# Water_Use_Monitor.net
KiCad netlist of a schematic drawn in EAGLE
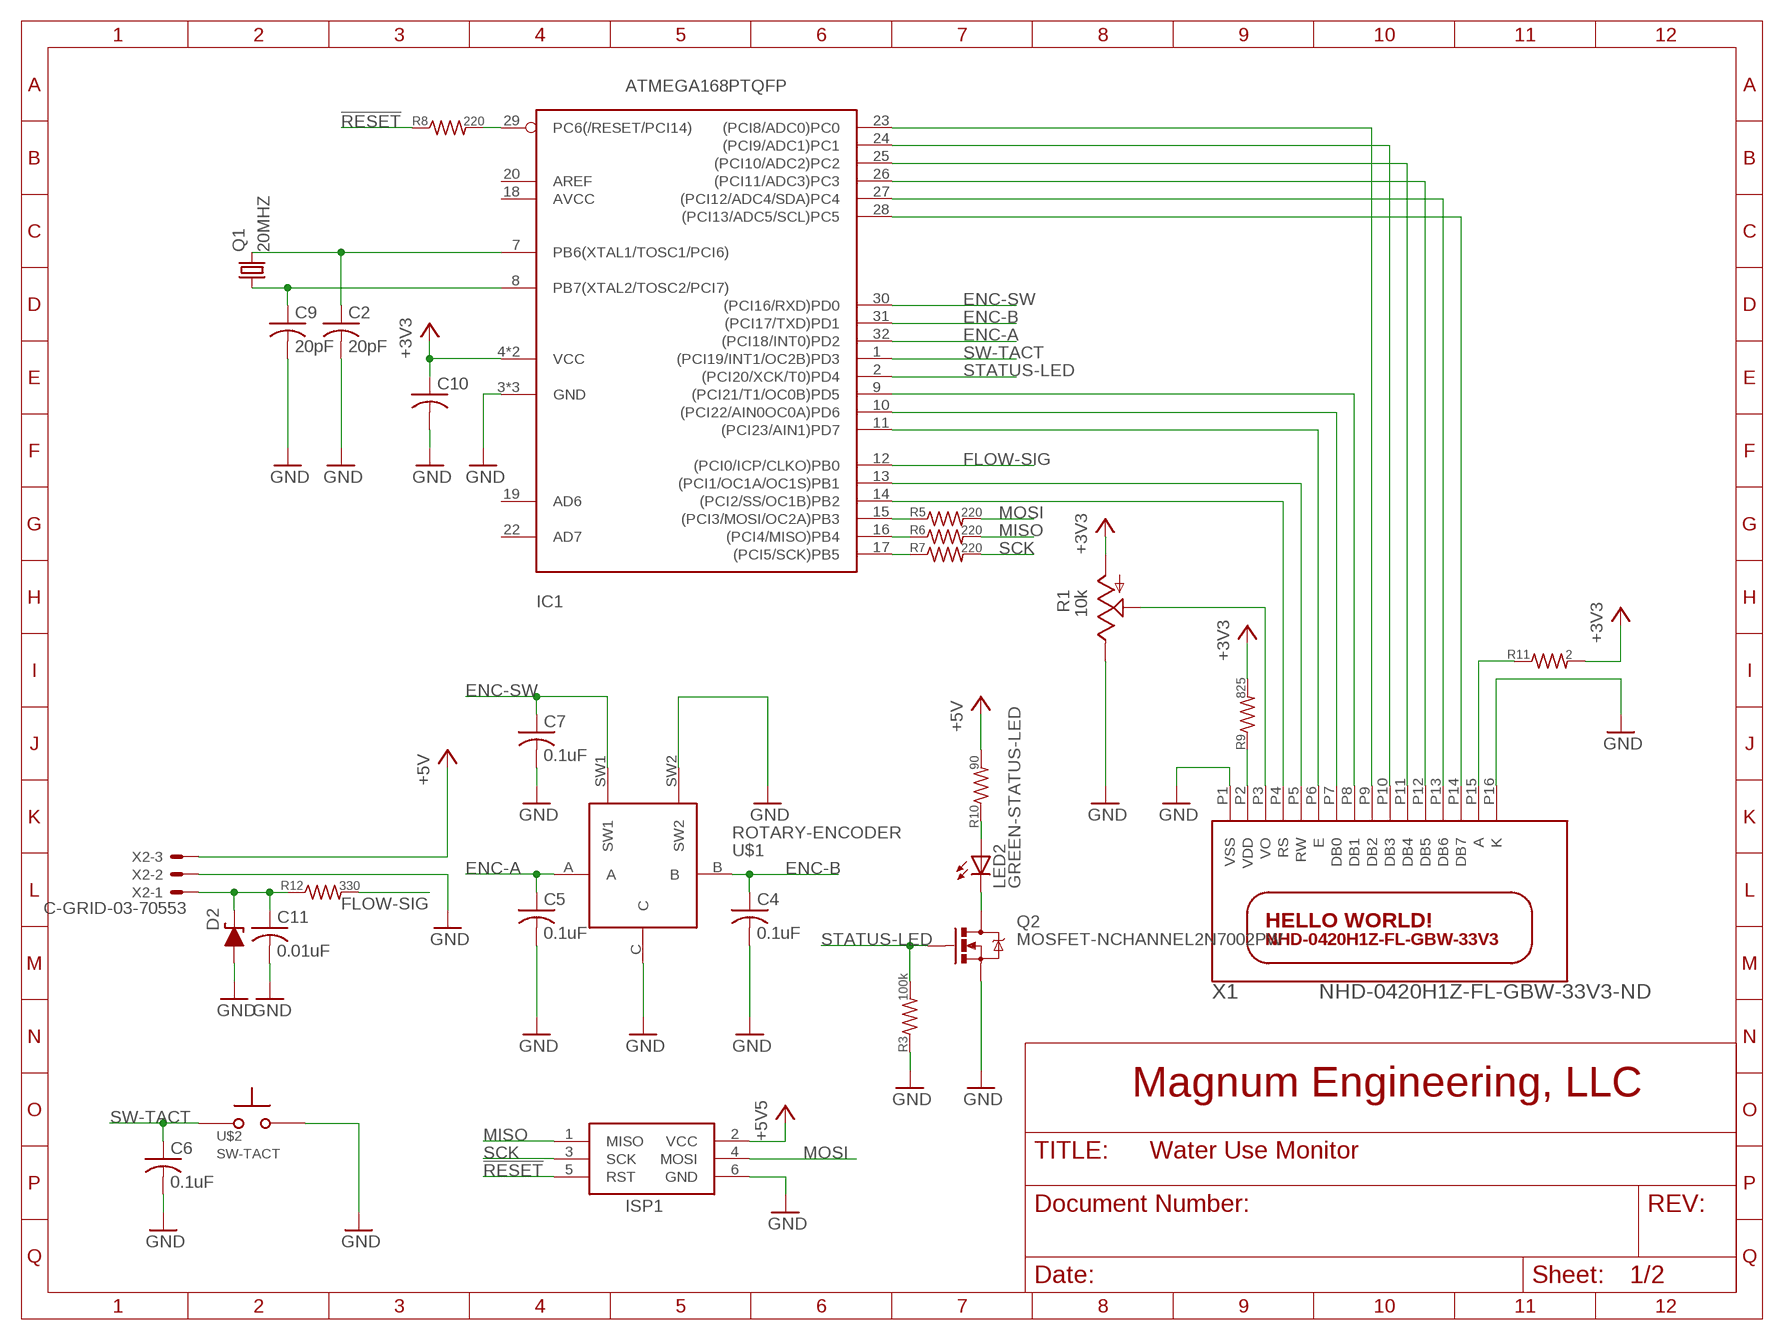
[diagram p0: schematic, sheet 1]
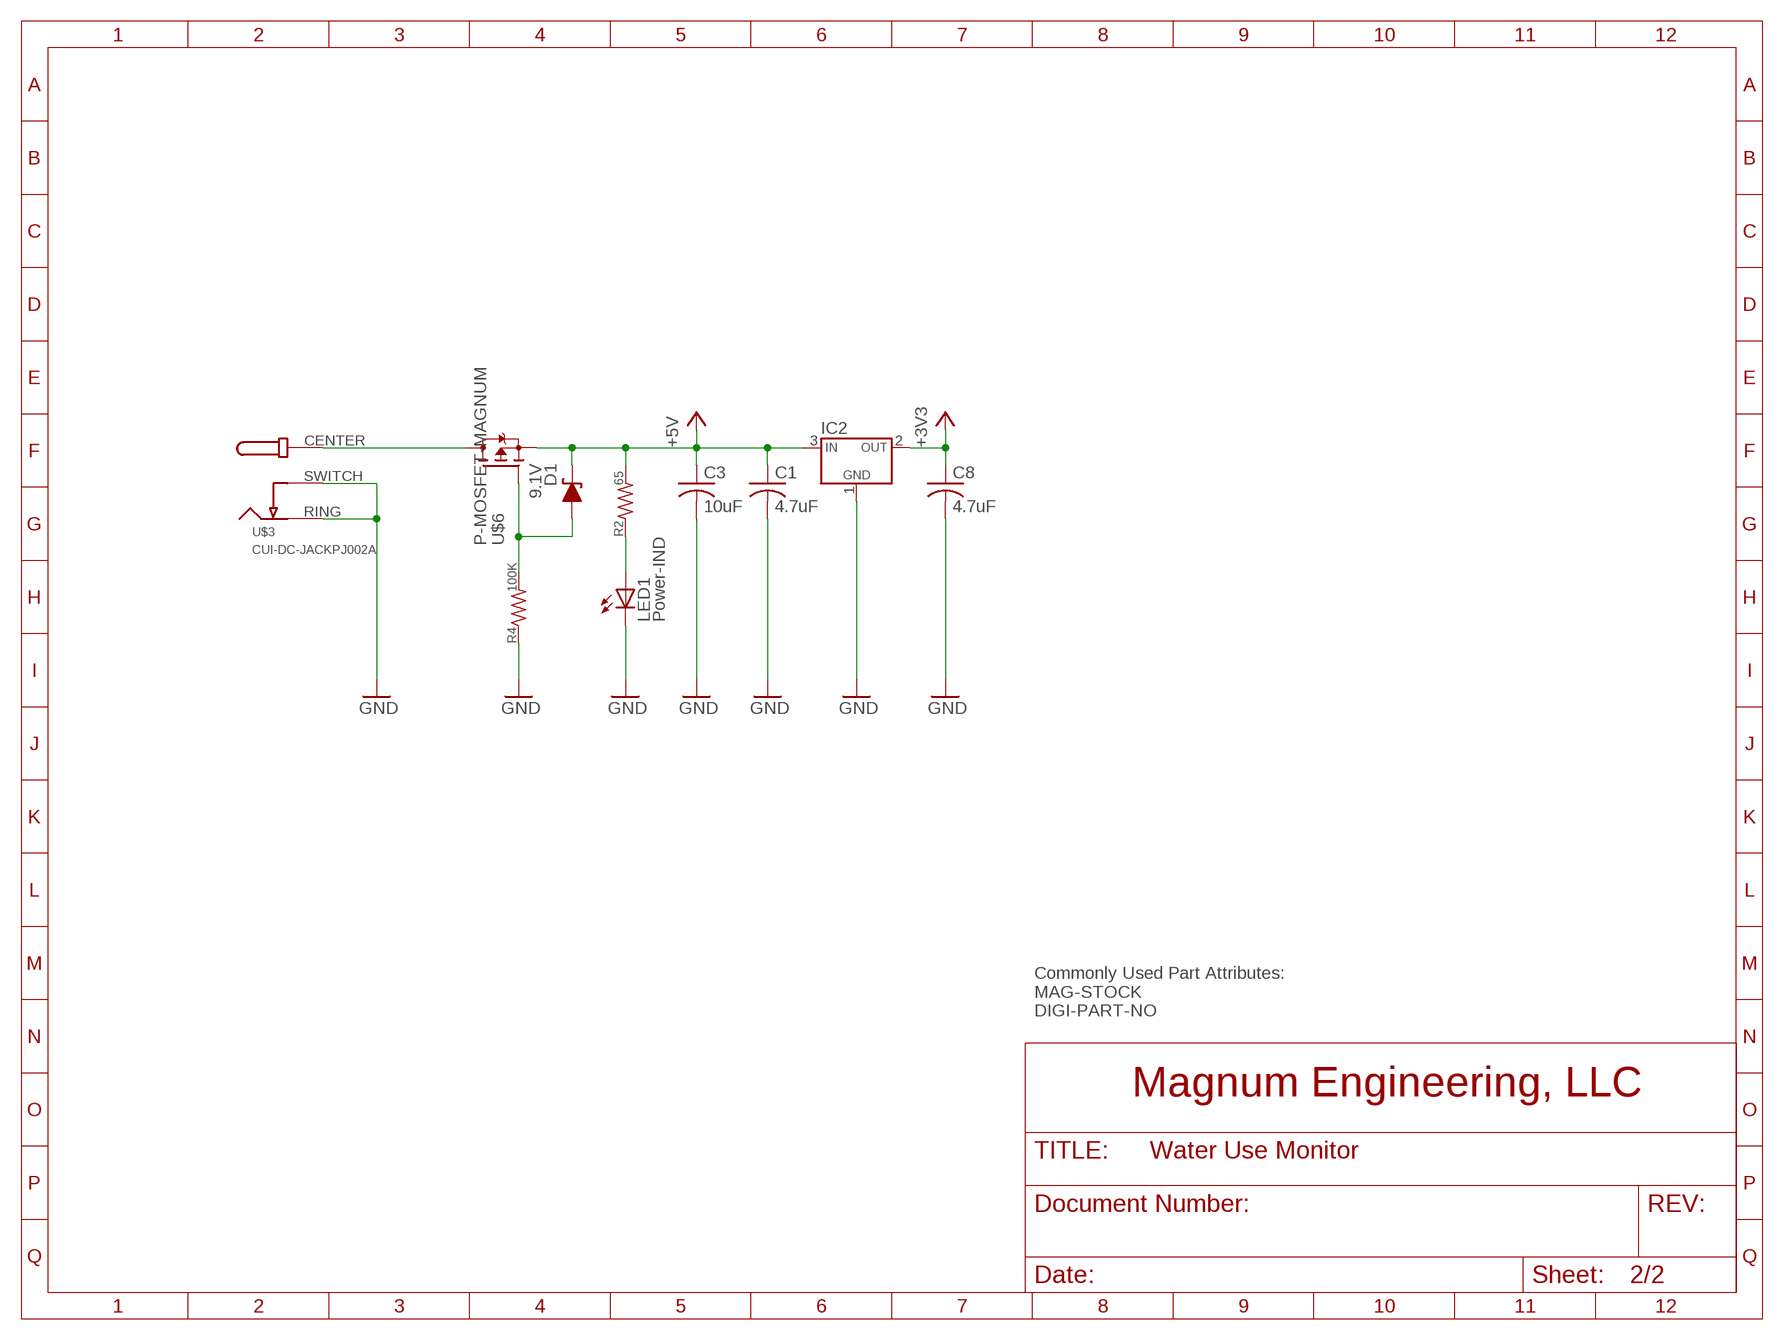
[diagram p1: schematic, sheet 2]

(export (version "E")
  (design (tool "Eeschema 10.0.6"))
  (components
    (comp (ref "C2")
      (value "20pF")
      (footprint "eagle-import:C0805")
      (libsource (lib "eagle-import") (part "CAPACITOR0805"))
    )
    (comp (ref "C4")
      (value "0.1uF")
      (footprint "eagle-import:C0805")
      (libsource (lib "eagle-import") (part "CAPACITOR0805"))
    )
    (comp (ref "C5")
      (value "0.1uF")
      (footprint "eagle-import:C0805")
      (libsource (lib "eagle-import") (part "CAPACITOR0805"))
    )
    (comp (ref "C6")
      (value "0.1uF")
      (footprint "eagle-import:C0805")
      (libsource (lib "eagle-import") (part "CAPACITOR0805"))
    )
    (comp (ref "C7")
      (value "0.1uF")
      (footprint "eagle-import:C0805")
      (libsource (lib "eagle-import") (part "CAPACITOR0805"))
    )
    (comp (ref "C9")
      (value "20pF")
      (footprint "eagle-import:C0805")
      (libsource (lib "eagle-import") (part "CAPACITOR0805"))
    )
    (comp (ref "C10")
      (value "CAPACITOR0805")
      (footprint "eagle-import:C0805")
      (libsource (lib "eagle-import") (part "CAPACITOR0805"))
    )
    (comp (ref "C11")
      (value "0.01uF")
      (footprint "eagle-import:C0805")
      (libsource (lib "eagle-import") (part "CAPACITOR0805"))
    )
    (comp (ref "D2")
      (value "ZENERSOD-123")
      (footprint "eagle-import:SOD-123")
      (libsource (lib "eagle-import") (part "ZENERSOD-123"))
    )
    (comp (ref "IC1")
      (value "ATMEGA168PTQFP")
      (footprint "eagle-import:ADS4_TQFP32-08")
      (libsource (lib "eagle-import") (part "ATMEGA168PTQFP"))
    )
    (comp (ref "ISP1")
      (value "AVRISP-6")
      (footprint "eagle-import:AVRISP")
      (libsource (lib "eagle-import") (part "AVRISP-6"))
    )
    (comp (ref "LED2")
      (value "GREEN-STATUS-LED")
      (footprint "eagle-import:LED5MM")
      (libsource (lib "eagle-import") (part "LED5MM"))
    )
    (comp (ref "Q1")
      (value "20MHZ")
      (footprint "eagle-import:20MHZ")
      (libsource (lib "eagle-import") (part "CRYSTAL"))
    )
    (comp (ref "Q2")
      (value "MOSFET-NCHANNEL2N7002PW")
      (footprint "eagle-import:SOT323")
      (libsource (lib "eagle-import") (part "MOSFET-NCHANNEL2N7002PW"))
    )
    (comp (ref "R1")
      (value "10k")
      (footprint "eagle-import:POT_RS3")
      (libsource (lib "eagle-import") (part "POTENTIOMETER"))
    )
    (comp (ref "R3")
      (value "100k")
      (footprint "eagle-import:R0805")
      (libsource (lib "eagle-import") (part "RESISTOR0805"))
    )
    (comp (ref "R5")
      (value "220")
      (footprint "eagle-import:R0805")
      (libsource (lib "eagle-import") (part "RESISTOR0805"))
    )
    (comp (ref "R6")
      (value "220")
      (footprint "eagle-import:R0805")
      (libsource (lib "eagle-import") (part "RESISTOR0805"))
    )
    (comp (ref "R7")
      (value "220")
      (footprint "eagle-import:R0805")
      (libsource (lib "eagle-import") (part "RESISTOR0805"))
    )
    (comp (ref "R8")
      (value "220")
      (footprint "eagle-import:R0805")
      (libsource (lib "eagle-import") (part "RESISTOR0805"))
    )
    (comp (ref "R9")
      (value "825")
      (footprint "eagle-import:R0805")
      (libsource (lib "eagle-import") (part "RESISTOR0805"))
    )
    (comp (ref "R10")
      (value "90")
      (footprint "eagle-import:R0805")
      (libsource (lib "eagle-import") (part "RESISTOR0805"))
    )
    (comp (ref "R11")
      (value "2")
      (footprint "eagle-import:R0805")
      (libsource (lib "eagle-import") (part "RESISTOR0805"))
    )
    (comp (ref "R12")
      (value "330")
      (footprint "eagle-import:R0805")
      (libsource (lib "eagle-import") (part "RESISTOR0805"))
    )
    (comp (ref "U$1")
      (value "ROTARY-ENCODER")
      (footprint "eagle-import:ROTARY-ENCODER")
      (libsource (lib "eagle-import") (part "ROTARY-ENCODER"))
    )
    (comp (ref "U$2")
      (value "SW-TACT")
      (footprint "eagle-import:FSM15JLH")
      (libsource (lib "eagle-import") (part "SW-TACT"))
    )
    (comp (ref "X1")
      (value "NHD-0420H1Z-FL-GBW-33V3-ND")
      (footprint "eagle-import:NEWHAVEN-LCD")
      (libsource (lib "eagle-import") (part "HD44780LCD"))
    )
    (comp (ref "X2")
      (value "C-GRID-03-70553")
      (footprint "eagle-import:70553-03")
      (libsource (lib "eagle-import") (part "C-GRID-03-70553"))
    )
    (comp (ref "C1")
      (value "4.7uF")
      (footprint "eagle-import:C0805")
      (libsource (lib "eagle-import") (part "CAPACITOR0805"))
    )
    (comp (ref "C3")
      (value "10uF")
      (footprint "eagle-import:C0805")
      (libsource (lib "eagle-import") (part "CAPACITOR0805"))
    )
    (comp (ref "C8")
      (value "4.7uF")
      (footprint "eagle-import:C0805")
      (libsource (lib "eagle-import") (part "CAPACITOR0805"))
    )
    (comp (ref "D1")
      (value "9.1V")
      (footprint "eagle-import:SOT-23")
      (libsource (lib "eagle-import") (part "ZENERSOT-23"))
    )
    (comp (ref "IC2")
      (value "VREGLD1117-XX")
      (footprint "eagle-import:DPAK")
      (libsource (lib "eagle-import") (part "VREGLD1117-XX"))
    )
    (comp (ref "LED1")
      (value "Power-IND")
      (footprint "eagle-import:LED5MM")
      (libsource (lib "eagle-import") (part "LED5MM"))
    )
    (comp (ref "R2")
      (value "65")
      (footprint "eagle-import:R0805")
      (libsource (lib "eagle-import") (part "RESISTOR0805"))
    )
    (comp (ref "R4")
      (value "100K")
      (footprint "eagle-import:R0805")
      (libsource (lib "eagle-import") (part "RESISTOR0805"))
    )
    (comp (ref "U$3")
      (value "CUI-DC-JACKPJ002A")
      (footprint "eagle-import:PJ002A")
      (libsource (lib "eagle-import") (part "CUI-DC-JACKPJ002A"))
    )
    (comp (ref "U$6")
      (value "P-MOSFET-MAGNUM")
      (footprint "eagle-import:SOT23")
      (libsource (lib "eagle-import") (part "P-MOSFET-MAGNUM"))
    )
  )
  (nets
    (net (code "1") (name "+3V3") (class "Default")
      (node (ref "C10") (pin "1") (pinfunction "1_1") (pintype "passive"))
      (node (ref "C8") (pin "1") (pinfunction "1_1") (pintype "passive"))
      (node (ref "IC1") (pin "4") (pinfunction "VCC_4") (pintype "bidirectional"))
      (node (ref "IC1") (pin "6") (pinfunction "VCC_6") (pintype "bidirectional"))
      (node (ref "IC2") (pin "2") (pinfunction "OUT_2") (pintype "passive"))
      (node (ref "R1") (pin "A") (pinfunction "A_A") (pintype "passive"))
      (node (ref "R11") (pin "2") (pinfunction "2_2") (pintype "passive"))
      (node (ref "R9") (pin "2") (pinfunction "2_2") (pintype "passive"))
    )
    (net (code "2") (name "+5V") (class "Default")
      (node (ref "C1") (pin "1") (pinfunction "1_1") (pintype "passive"))
      (node (ref "C3") (pin "1") (pinfunction "1_1") (pintype "passive"))
      (node (ref "D1") (pin "3") (pinfunction "K_3") (pintype "passive"))
      (node (ref "IC2") (pin "3") (pinfunction "IN_3") (pintype "passive"))
      (node (ref "R10") (pin "2") (pinfunction "2_2") (pintype "passive"))
      (node (ref "R2") (pin "2") (pinfunction "2_2") (pintype "passive"))
      (node (ref "U$6") (pin "2") (pinfunction "S_2") (pintype "passive"))
      (node (ref "X2") (pin "3") (pinfunction "S_3") (pintype "passive"))
    )
    (net (code "3") (name "+5V5") (class "Default")
      (node (ref "ISP1") (pin "2") (pinfunction "VCC_2") (pintype "power_in"))
    )
    (net (code "4") (name "ENC-A") (class "Default")
      (node (ref "C5") (pin "1") (pinfunction "1_1") (pintype "passive"))
      (node (ref "IC1") (pin "32") (pinfunction "(PCI18/INT0)PD2_32") (pintype "bidirectional"))
      (node (ref "U$1") (pin "A") (pinfunction "A_A") (pintype "bidirectional"))
    )
    (net (code "5") (name "ENC-B") (class "Default")
      (node (ref "C4") (pin "1") (pinfunction "1_1") (pintype "passive"))
      (node (ref "IC1") (pin "31") (pinfunction "(PCI17/TXD)PD1_31") (pintype "bidirectional"))
      (node (ref "U$1") (pin "B") (pinfunction "B_B") (pintype "bidirectional"))
    )
    (net (code "6") (name "ENC-SW") (class "Default")
      (node (ref "C7") (pin "1") (pinfunction "1_1") (pintype "passive"))
      (node (ref "IC1") (pin "30") (pinfunction "(PCI16/RXD)PD0_30") (pintype "bidirectional"))
      (node (ref "U$1") (pin "SW1") (pinfunction "SW1_SW1") (pintype "bidirectional"))
    )
    (net (code "7") (name "FLOW-SIG") (class "Default")
      (node (ref "IC1") (pin "12") (pinfunction "(PCI0/ICP/CLKO)PB0_12") (pintype "bidirectional"))
      (node (ref "R12") (pin "2") (pinfunction "2_2") (pintype "passive"))
    )
    (net (code "8") (name "GND") (class "Default")
      (node (ref "C1") (pin "2") (pinfunction "2_2") (pintype "passive"))
      (node (ref "C10") (pin "2") (pinfunction "2_2") (pintype "passive"))
      (node (ref "C11") (pin "2") (pinfunction "2_2") (pintype "passive"))
      (node (ref "C2") (pin "2") (pinfunction "2_2") (pintype "passive"))
      (node (ref "C3") (pin "2") (pinfunction "2_2") (pintype "passive"))
      (node (ref "C4") (pin "2") (pinfunction "2_2") (pintype "passive"))
      (node (ref "C5") (pin "2") (pinfunction "2_2") (pintype "passive"))
      (node (ref "C6") (pin "2") (pinfunction "2_2") (pintype "passive"))
      (node (ref "C7") (pin "2") (pinfunction "2_2") (pintype "passive"))
      (node (ref "C8") (pin "2") (pinfunction "2_2") (pintype "passive"))
      (node (ref "C9") (pin "2") (pinfunction "2_2") (pintype "passive"))
      (node (ref "D2") (pin "A") (pinfunction "A_A") (pintype "passive"))
      (node (ref "IC1") (pin "21") (pinfunction "GND_21") (pintype "bidirectional"))
      (node (ref "IC1") (pin "3") (pinfunction "GND_3") (pintype "bidirectional"))
      (node (ref "IC1") (pin "5") (pinfunction "GND_5") (pintype "bidirectional"))
      (node (ref "IC2") (pin "1") (pinfunction "GND_1") (pintype "passive"))
      (node (ref "ISP1") (pin "6") (pinfunction "GND_6") (pintype "power_in"))
      (node (ref "LED1") (pin "K") (pinfunction "C_K") (pintype "passive"))
      (node (ref "Q2") (pin "2") (pinfunction "S_2") (pintype "passive"))
      (node (ref "R1") (pin "E") (pinfunction "E_E") (pintype "passive"))
      (node (ref "R3") (pin "1") (pinfunction "1_1") (pintype "passive"))
      (node (ref "R4") (pin "1") (pinfunction "1_1") (pintype "passive"))
      (node (ref "U$1") (pin "C") (pinfunction "C_C") (pintype "bidirectional"))
      (node (ref "U$1") (pin "SW2") (pinfunction "SW2_SW2") (pintype "bidirectional"))
      (node (ref "U$2") (pin "P$3") (pinfunction "P$2_P$3") (pintype "bidirectional"))
      (node (ref "U$2") (pin "P$4") (pinfunction "P$2_P$4") (pintype "bidirectional"))
      (node (ref "U$3") (pin "RING") (pinfunction "RING_RING") (pintype "bidirectional"))
      (node (ref "U$3") (pin "SWITCH") (pinfunction "SW_SWITCH") (pintype "bidirectional"))
      (node (ref "X1") (pin "P1") (pinfunction "VSS_P1") (pintype "power_in"))
      (node (ref "X1") (pin "P16") (pinfunction "K_P16") (pintype "input"))
      (node (ref "X2") (pin "2") (pinfunction "S_2") (pintype "passive"))
    )
    (net (code "9") (name "MISO") (class "Default")
      (node (ref "ISP1") (pin "1") (pinfunction "MISO_1") (pintype "input"))
      (node (ref "R6") (pin "2") (pinfunction "2_2") (pintype "passive"))
    )
    (net (code "10") (name "MOSI") (class "Default")
      (node (ref "ISP1") (pin "4") (pinfunction "MOSI_4") (pintype "output"))
      (node (ref "R5") (pin "2") (pinfunction "2_2") (pintype "passive"))
    )
    (net (code "11") (name "Net-(D1-A)") (class "Default")
      (node (ref "D1") (pin "1") (pinfunction "A_1") (pintype "passive"))
      (node (ref "R4") (pin "2") (pinfunction "2_2") (pintype "passive"))
      (node (ref "U$6") (pin "1") (pinfunction "G_1") (pintype "passive"))
    )
    (net (code "12") (name "Net-(IC1-(PCI1{slash}OC1A{slash}OC1S)PB1)") (class "Default")
      (node (ref "IC1") (pin "13") (pinfunction "(PCI1/OC1A/OC1S)PB1_13") (pintype "bidirectional"))
      (node (ref "X1") (pin "P5") (pinfunction "RW_P5") (pintype "input"))
    )
    (net (code "13") (name "Net-(IC1-(PCI2{slash}SS{slash}OC1B)PB2)") (class "Default")
      (node (ref "IC1") (pin "14") (pinfunction "(PCI2/SS/OC1B)PB2_14") (pintype "bidirectional"))
      (node (ref "X1") (pin "P4") (pinfunction "RS_P4") (pintype "input"))
    )
    (net (code "14") (name "Net-(IC1-(PCI3{slash}MOSI{slash}OC2A)PB3)") (class "Default")
      (node (ref "IC1") (pin "15") (pinfunction "(PCI3/MOSI/OC2A)PB3_15") (pintype "bidirectional"))
      (node (ref "R5") (pin "1") (pinfunction "1_1") (pintype "passive"))
    )
    (net (code "15") (name "Net-(IC1-(PCI4{slash}MISO)PB4)") (class "Default")
      (node (ref "IC1") (pin "16") (pinfunction "(PCI4/MISO)PB4_16") (pintype "bidirectional"))
      (node (ref "R6") (pin "1") (pinfunction "1_1") (pintype "passive"))
    )
    (net (code "16") (name "Net-(IC1-(PCI5{slash}SCK)PB5)") (class "Default")
      (node (ref "IC1") (pin "17") (pinfunction "(PCI5/SCK)PB5_17") (pintype "bidirectional"))
      (node (ref "R7") (pin "1") (pinfunction "1_1") (pintype "passive"))
    )
    (net (code "17") (name "Net-(IC1-(PCI8{slash}ADC0)PC0)") (class "Default")
      (node (ref "IC1") (pin "23") (pinfunction "(PCI8/ADC0)PC0_23") (pintype "bidirectional"))
      (node (ref "X1") (pin "P9") (pinfunction "DB2_P9") (pintype "bidirectional"))
    )
    (net (code "18") (name "Net-(IC1-(PCI9{slash}ADC1)PC1)") (class "Default")
      (node (ref "IC1") (pin "24") (pinfunction "(PCI9/ADC1)PC1_24") (pintype "bidirectional"))
      (node (ref "X1") (pin "P10") (pinfunction "DB3_P10") (pintype "bidirectional"))
    )
    (net (code "19") (name "Net-(IC1-(PCI10{slash}ADC2)PC2)") (class "Default")
      (node (ref "IC1") (pin "25") (pinfunction "(PCI10/ADC2)PC2_25") (pintype "bidirectional"))
      (node (ref "X1") (pin "P11") (pinfunction "DB4_P11") (pintype "bidirectional"))
    )
    (net (code "20") (name "Net-(IC1-(PCI11{slash}ADC3)PC3)") (class "Default")
      (node (ref "IC1") (pin "26") (pinfunction "(PCI11/ADC3)PC3_26") (pintype "bidirectional"))
      (node (ref "X1") (pin "P12") (pinfunction "DB5_P12") (pintype "bidirectional"))
    )
    (net (code "21") (name "Net-(IC1-(PCI12{slash}ADC4{slash}SDA)PC4)") (class "Default")
      (node (ref "IC1") (pin "27") (pinfunction "(PCI12/ADC4/SDA)PC4_27") (pintype "bidirectional"))
      (node (ref "X1") (pin "P13") (pinfunction "DB6_P13") (pintype "bidirectional"))
    )
    (net (code "22") (name "Net-(IC1-(PCI13{slash}ADC5{slash}SCL)PC5)") (class "Default")
      (node (ref "IC1") (pin "28") (pinfunction "(PCI13/ADC5/SCL)PC5_28") (pintype "bidirectional"))
      (node (ref "X1") (pin "P14") (pinfunction "DB7_P14") (pintype "bidirectional"))
    )
    (net (code "23") (name "Net-(IC1-(PCI21{slash}T1{slash}OC0B)PD5)") (class "Default")
      (node (ref "IC1") (pin "9") (pinfunction "(PCI21/T1/OC0B)PD5_9") (pintype "bidirectional"))
      (node (ref "X1") (pin "P8") (pinfunction "DB1_P8") (pintype "bidirectional"))
    )
    (net (code "24") (name "Net-(IC1-(PCI22{slash}AIN0OC0A)PD6)") (class "Default")
      (node (ref "IC1") (pin "10") (pinfunction "(PCI22/AIN0OC0A)PD6_10") (pintype "bidirectional"))
      (node (ref "X1") (pin "P7") (pinfunction "DB0_P7") (pintype "bidirectional"))
    )
    (net (code "25") (name "Net-(IC1-(PCI23{slash}AIN1)PD7)") (class "Default")
      (node (ref "IC1") (pin "11") (pinfunction "(PCI23/AIN1)PD7_11") (pintype "bidirectional"))
      (node (ref "X1") (pin "P6") (pinfunction "E_P6") (pintype "input"))
    )
    (net (code "26") (name "Net-(IC1-PB6(XTAL1{slash}TOSC1{slash}PCI6))") (class "Default")
      (node (ref "C2") (pin "1") (pinfunction "1_1") (pintype "passive"))
      (node (ref "IC1") (pin "7") (pinfunction "PB6(XTAL1/TOSC1/PCI6)_7") (pintype "bidirectional"))
      (node (ref "Q1") (pin "P$2") (pinfunction "2_P$2") (pintype "passive"))
    )
    (net (code "27") (name "Net-(IC1-PB7(XTAL2{slash}TOSC2{slash}PCI7))") (class "Default")
      (node (ref "C9") (pin "1") (pinfunction "1_1") (pintype "passive"))
      (node (ref "IC1") (pin "8") (pinfunction "PB7(XTAL2/TOSC2/PCI7)_8") (pintype "bidirectional"))
      (node (ref "Q1") (pin "P$1") (pinfunction "1_P$1") (pintype "passive"))
    )
    (net (code "28") (name "Net-(IC1-PC6({slash}RESET{slash}PCI14))") (class "Default")
      (node (ref "IC1") (pin "29") (pinfunction "PC6(/RESET/PCI14)_29") (pintype "bidirectional"))
      (node (ref "R8") (pin "2") (pinfunction "2_2") (pintype "passive"))
    )
    (net (code "29") (name "Net-(LED1-PadA)") (class "Default")
      (node (ref "LED1") (pin "A") (pinfunction "A_A") (pintype "passive"))
      (node (ref "R2") (pin "1") (pinfunction "1_1") (pintype "passive"))
    )
    (net (code "30") (name "Net-(LED2-C)") (class "Default")
      (node (ref "LED2") (pin "K") (pinfunction "C_K") (pintype "passive"))
      (node (ref "Q2") (pin "3") (pinfunction "D_3") (pintype "passive"))
    )
    (net (code "31") (name "Net-(LED2-PadA)") (class "Default")
      (node (ref "LED2") (pin "A") (pinfunction "A_A") (pintype "passive"))
      (node (ref "R10") (pin "1") (pinfunction "1_1") (pintype "passive"))
    )
    (net (code "32") (name "Net-(U$6-D)") (class "Default")
      (node (ref "U$3") (pin "CENTER") (pinfunction "CENTER_CENTER") (pintype "bidirectional"))
      (node (ref "U$6") (pin "3") (pinfunction "D_3") (pintype "passive"))
    )
    (net (code "33") (name "Net-(X1-A)") (class "Default")
      (node (ref "R11") (pin "1") (pinfunction "1_1") (pintype "passive"))
      (node (ref "X1") (pin "P15") (pinfunction "A_P15") (pintype "input"))
    )
    (net (code "34") (name "Net-(X1-VDD)") (class "Default")
      (node (ref "R9") (pin "1") (pinfunction "1_1") (pintype "passive"))
      (node (ref "X1") (pin "P2") (pinfunction "VDD_P2") (pintype "power_in"))
    )
    (net (code "35") (name "Net-(X1-VO)") (class "Default")
      (node (ref "R1") (pin "S") (pinfunction "S_S") (pintype "passive"))
      (node (ref "X1") (pin "P3") (pinfunction "VO_P3") (pintype "input"))
    )
    (net (code "36") (name "Net-(X2A-S)") (class "Default")
      (node (ref "C11") (pin "1") (pinfunction "1_1") (pintype "passive"))
      (node (ref "D2") (pin "K") (pinfunction "K_K") (pintype "passive"))
      (node (ref "R12") (pin "1") (pinfunction "1_1") (pintype "passive"))
      (node (ref "X2") (pin "1") (pinfunction "S_1") (pintype "passive"))
    )
    (net (code "37") (name "SCK") (class "Default")
      (node (ref "ISP1") (pin "3") (pinfunction "SCK_3") (pintype "output"))
      (node (ref "R7") (pin "2") (pinfunction "2_2") (pintype "passive"))
    )
    (net (code "38") (name "STATUS-LED") (class "Default")
      (node (ref "IC1") (pin "2") (pinfunction "(PCI20/XCK/T0)PD4_2") (pintype "bidirectional"))
      (node (ref "Q2") (pin "1") (pinfunction "G_1") (pintype "passive"))
      (node (ref "R3") (pin "2") (pinfunction "2_2") (pintype "passive"))
    )
    (net (code "39") (name "SW-TACT") (class "Default")
      (node (ref "C6") (pin "1") (pinfunction "1_1") (pintype "passive"))
      (node (ref "IC1") (pin "1") (pinfunction "(PCI19/INT1/OC2B)PD3_1") (pintype "bidirectional"))
      (node (ref "U$2") (pin "P$1") (pinfunction "P$1_P$1") (pintype "bidirectional"))
      (node (ref "U$2") (pin "P$2") (pinfunction "P$1_P$2") (pintype "bidirectional"))
    )
    (net (code "40") (name "unconnected-(IC1-AD6-Pad19)") (class "Default")
      (node (ref "IC1") (pin "19") (pinfunction "AD6_19") (pintype "bidirectional"))
    )
    (net (code "41") (name "unconnected-(IC1-AD7-Pad22)") (class "Default")
      (node (ref "IC1") (pin "22") (pinfunction "AD7_22") (pintype "bidirectional"))
    )
    (net (code "42") (name "unconnected-(IC1-AREF-Pad20)") (class "Default")
      (node (ref "IC1") (pin "20") (pinfunction "AREF_20") (pintype "bidirectional"))
    )
    (net (code "43") (name "unconnected-(IC1-AVCC-Pad18)") (class "Default")
      (node (ref "IC1") (pin "18") (pinfunction "AVCC_18") (pintype "bidirectional"))
    )
    (net (code "44") (name "~{RESET}") (class "Default")
      (node (ref "ISP1") (pin "5") (pinfunction "RST_5") (pintype "output"))
      (node (ref "R8") (pin "1") (pinfunction "1_1") (pintype "passive"))
    )
  )
)
